# NixieDriver_overkill.net
KiCad netlist of a schematic drawn in EAGLE
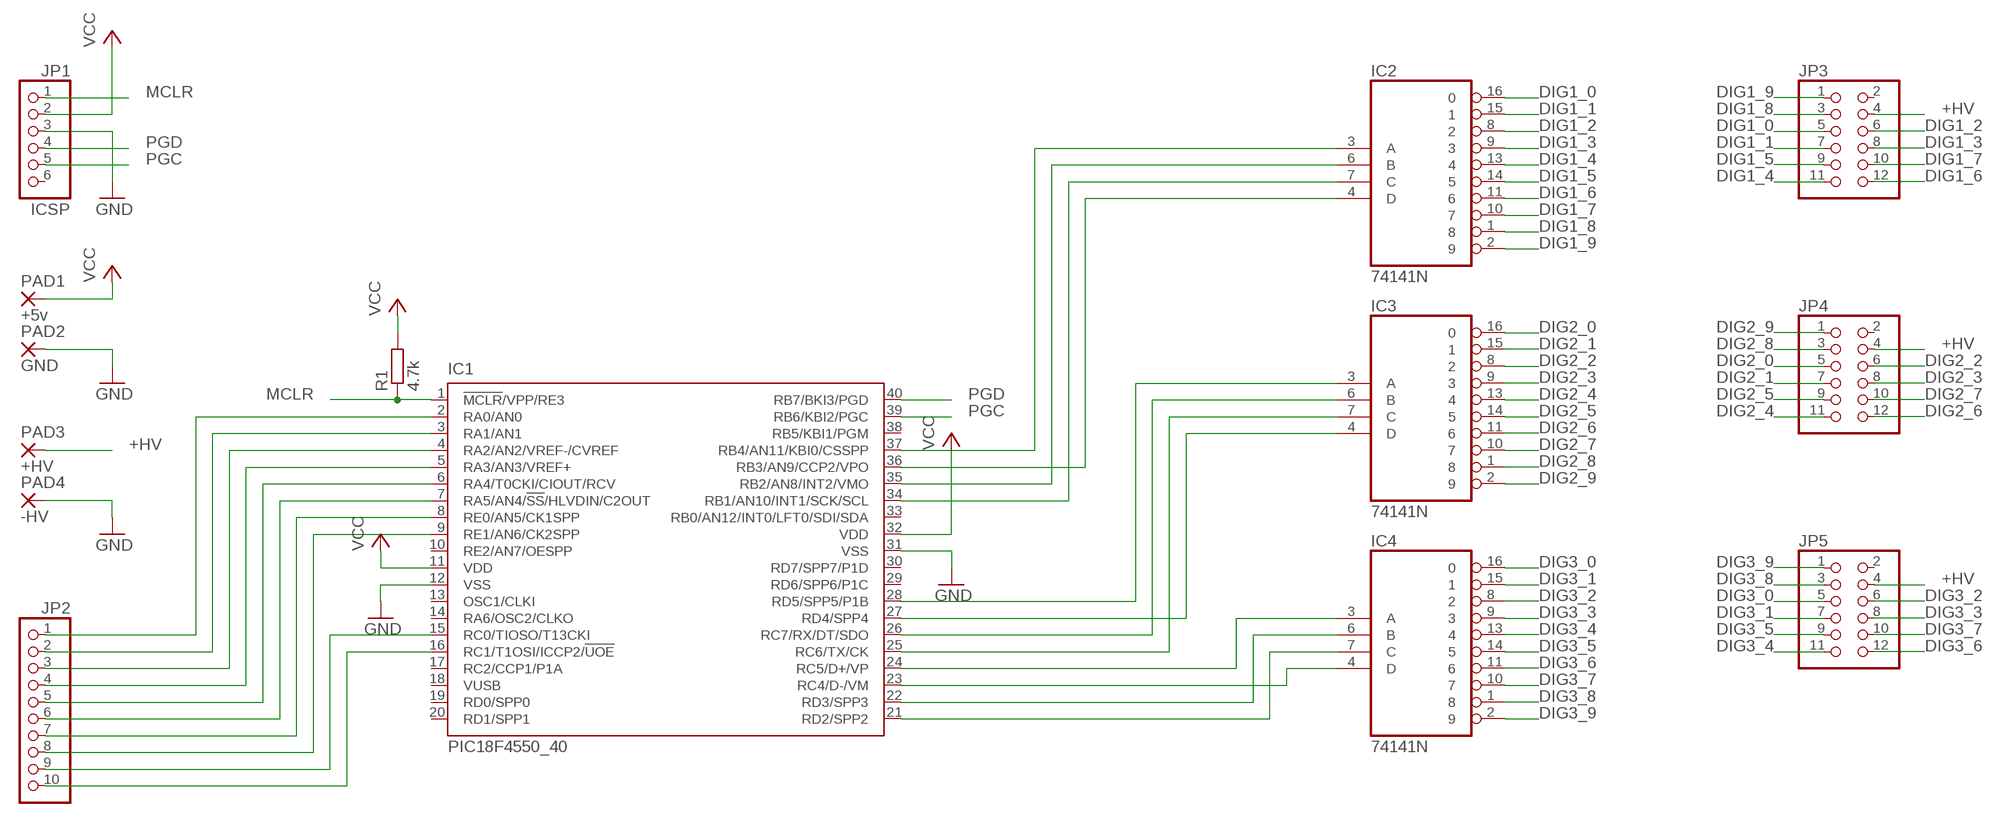
[diagram p0: schematic, sheet 1]

(export (version "E")
  (design (tool "Eeschema 10.0.6"))
  (components
    (comp (ref "IC1")
      (value "PIC18F4550_40")
      (footprint "eagle-import:DIL40")
      (fields (field (name "MF") "MICROCHIP") (field (name "MPN") "PIC18F4550-I/P"))
      (libsource (lib "eagle-import") (part "PIC18F4_40550"))
    )
    (comp (ref "IC2")
      (value "74141N")
      (footprint "eagle-import:DIL16")
      (libsource (lib "eagle-import") (part "74141N"))
    )
    (comp (ref "IC3")
      (value "74141N")
      (footprint "eagle-import:DIL16")
      (libsource (lib "eagle-import") (part "74141N"))
    )
    (comp (ref "IC4")
      (value "74141N")
      (footprint "eagle-import:DIL16")
      (libsource (lib "eagle-import") (part "74141N"))
    )
    (comp (ref "JP1")
      (value "ICSP")
      (footprint "eagle-import:1X06")
      (libsource (lib "eagle-import") (part "PINHD-1X6"))
    )
    (comp (ref "JP2")
      (value "PINHD-1X10")
      (footprint "eagle-import:1X10")
      (libsource (lib "eagle-import") (part "PINHD-1X10"))
    )
    (comp (ref "JP3")
      (value "PINHD-2X6")
      (footprint "eagle-import:2X06")
      (libsource (lib "eagle-import") (part "PINHD-2X6"))
    )
    (comp (ref "JP4")
      (value "PINHD-2X6")
      (footprint "eagle-import:2X06")
      (libsource (lib "eagle-import") (part "PINHD-2X6"))
    )
    (comp (ref "JP5")
      (value "PINHD-2X6")
      (footprint "eagle-import:2X06")
      (libsource (lib "eagle-import") (part "PINHD-2X6"))
    )
    (comp (ref "PAD1")
      (value "+5v")
      (footprint "eagle-import:SMD2,54-5,08")
      (libsource (lib "eagle-import") (part "SMD5"))
    )
    (comp (ref "PAD2")
      (value "GND")
      (footprint "eagle-import:SMD2,54-5,08")
      (libsource (lib "eagle-import") (part "SMD5"))
    )
    (comp (ref "PAD3")
      (value "+HV")
      (footprint "eagle-import:SMD2,54-5,08")
      (libsource (lib "eagle-import") (part "SMD5"))
    )
    (comp (ref "PAD4")
      (value "-HV")
      (footprint "eagle-import:SMD2,54-5,08")
      (libsource (lib "eagle-import") (part "SMD5"))
    )
    (comp (ref "R1")
      (value "4.7k")
      (footprint "eagle-import:R1206")
      (libsource (lib "eagle-import") (part "R-EU_R1206"))
    )
  )
  (nets
    (net (code "1") (name "/+HV") (class "Default")
      (node (ref "JP3") (pin "4") (pinfunction "4_4") (pintype "passive"))
      (node (ref "JP4") (pin "4") (pinfunction "4_4") (pintype "passive"))
      (node (ref "JP5") (pin "4") (pinfunction "4_4") (pintype "passive"))
      (node (ref "PAD3") (pin "1") (pinfunction "P_1") (pintype "passive"))
    )
    (net (code "2") (name "/DIG1_0") (class "Default")
      (node (ref "IC2") (pin "16") (pinfunction "0_16") (pintype "open_collector"))
      (node (ref "JP3") (pin "5") (pinfunction "5_5") (pintype "passive"))
    )
    (net (code "3") (name "/DIG1_1") (class "Default")
      (node (ref "IC2") (pin "15") (pinfunction "1_15") (pintype "open_collector"))
      (node (ref "JP3") (pin "7") (pinfunction "7_7") (pintype "passive"))
    )
    (net (code "4") (name "/DIG1_2") (class "Default")
      (node (ref "IC2") (pin "8") (pinfunction "2_8") (pintype "open_collector"))
      (node (ref "JP3") (pin "6") (pinfunction "6_6") (pintype "passive"))
    )
    (net (code "5") (name "/DIG1_3") (class "Default")
      (node (ref "IC2") (pin "9") (pinfunction "3_9") (pintype "open_collector"))
      (node (ref "JP3") (pin "8") (pinfunction "8_8") (pintype "passive"))
    )
    (net (code "6") (name "/DIG1_4") (class "Default")
      (node (ref "IC2") (pin "13") (pinfunction "4_13") (pintype "open_collector"))
      (node (ref "JP3") (pin "11") (pinfunction "11_11") (pintype "passive"))
    )
    (net (code "7") (name "/DIG1_5") (class "Default")
      (node (ref "IC2") (pin "14") (pinfunction "5_14") (pintype "open_collector"))
      (node (ref "JP3") (pin "9") (pinfunction "9_9") (pintype "passive"))
    )
    (net (code "8") (name "/DIG1_6") (class "Default")
      (node (ref "IC2") (pin "11") (pinfunction "6_11") (pintype "open_collector"))
      (node (ref "JP3") (pin "12") (pinfunction "12_12") (pintype "passive"))
    )
    (net (code "9") (name "/DIG1_7") (class "Default")
      (node (ref "IC2") (pin "10") (pinfunction "7_10") (pintype "open_collector"))
      (node (ref "JP3") (pin "10") (pinfunction "10_10") (pintype "passive"))
    )
    (net (code "10") (name "/DIG1_8") (class "Default")
      (node (ref "IC2") (pin "1") (pinfunction "8_1") (pintype "open_collector"))
      (node (ref "JP3") (pin "3") (pinfunction "3_3") (pintype "passive"))
    )
    (net (code "11") (name "/DIG1_9") (class "Default")
      (node (ref "IC2") (pin "2") (pinfunction "9_2") (pintype "open_collector"))
      (node (ref "JP3") (pin "1") (pinfunction "1_1") (pintype "passive"))
    )
    (net (code "12") (name "/DIG2_0") (class "Default")
      (node (ref "IC3") (pin "16") (pinfunction "0_16") (pintype "open_collector"))
      (node (ref "JP4") (pin "5") (pinfunction "5_5") (pintype "passive"))
    )
    (net (code "13") (name "/DIG2_1") (class "Default")
      (node (ref "IC3") (pin "15") (pinfunction "1_15") (pintype "open_collector"))
      (node (ref "JP4") (pin "7") (pinfunction "7_7") (pintype "passive"))
    )
    (net (code "14") (name "/DIG2_2") (class "Default")
      (node (ref "IC3") (pin "8") (pinfunction "2_8") (pintype "open_collector"))
      (node (ref "JP4") (pin "6") (pinfunction "6_6") (pintype "passive"))
    )
    (net (code "15") (name "/DIG2_3") (class "Default")
      (node (ref "IC3") (pin "9") (pinfunction "3_9") (pintype "open_collector"))
      (node (ref "JP4") (pin "8") (pinfunction "8_8") (pintype "passive"))
    )
    (net (code "16") (name "/DIG2_4") (class "Default")
      (node (ref "IC3") (pin "13") (pinfunction "4_13") (pintype "open_collector"))
      (node (ref "JP4") (pin "11") (pinfunction "11_11") (pintype "passive"))
    )
    (net (code "17") (name "/DIG2_5") (class "Default")
      (node (ref "IC3") (pin "14") (pinfunction "5_14") (pintype "open_collector"))
      (node (ref "JP4") (pin "9") (pinfunction "9_9") (pintype "passive"))
    )
    (net (code "18") (name "/DIG2_6") (class "Default")
      (node (ref "IC3") (pin "11") (pinfunction "6_11") (pintype "open_collector"))
      (node (ref "JP4") (pin "12") (pinfunction "12_12") (pintype "passive"))
    )
    (net (code "19") (name "/DIG2_7") (class "Default")
      (node (ref "IC3") (pin "10") (pinfunction "7_10") (pintype "open_collector"))
      (node (ref "JP4") (pin "10") (pinfunction "10_10") (pintype "passive"))
    )
    (net (code "20") (name "/DIG2_8") (class "Default")
      (node (ref "IC3") (pin "1") (pinfunction "8_1") (pintype "open_collector"))
      (node (ref "JP4") (pin "3") (pinfunction "3_3") (pintype "passive"))
    )
    (net (code "21") (name "/DIG2_9") (class "Default")
      (node (ref "IC3") (pin "2") (pinfunction "9_2") (pintype "open_collector"))
      (node (ref "JP4") (pin "1") (pinfunction "1_1") (pintype "passive"))
    )
    (net (code "22") (name "/DIG3_0") (class "Default")
      (node (ref "IC4") (pin "16") (pinfunction "0_16") (pintype "open_collector"))
      (node (ref "JP5") (pin "5") (pinfunction "5_5") (pintype "passive"))
    )
    (net (code "23") (name "/DIG3_1") (class "Default")
      (node (ref "IC4") (pin "15") (pinfunction "1_15") (pintype "open_collector"))
      (node (ref "JP5") (pin "7") (pinfunction "7_7") (pintype "passive"))
    )
    (net (code "24") (name "/DIG3_2") (class "Default")
      (node (ref "IC4") (pin "8") (pinfunction "2_8") (pintype "open_collector"))
      (node (ref "JP5") (pin "6") (pinfunction "6_6") (pintype "passive"))
    )
    (net (code "25") (name "/DIG3_3") (class "Default")
      (node (ref "IC4") (pin "9") (pinfunction "3_9") (pintype "open_collector"))
      (node (ref "JP5") (pin "8") (pinfunction "8_8") (pintype "passive"))
    )
    (net (code "26") (name "/DIG3_4") (class "Default")
      (node (ref "IC4") (pin "13") (pinfunction "4_13") (pintype "open_collector"))
      (node (ref "JP5") (pin "11") (pinfunction "11_11") (pintype "passive"))
    )
    (net (code "27") (name "/DIG3_5") (class "Default")
      (node (ref "IC4") (pin "14") (pinfunction "5_14") (pintype "open_collector"))
      (node (ref "JP5") (pin "9") (pinfunction "9_9") (pintype "passive"))
    )
    (net (code "28") (name "/DIG3_6") (class "Default")
      (node (ref "IC4") (pin "11") (pinfunction "6_11") (pintype "open_collector"))
      (node (ref "JP5") (pin "12") (pinfunction "12_12") (pintype "passive"))
    )
    (net (code "29") (name "/DIG3_7") (class "Default")
      (node (ref "IC4") (pin "10") (pinfunction "7_10") (pintype "open_collector"))
      (node (ref "JP5") (pin "10") (pinfunction "10_10") (pintype "passive"))
    )
    (net (code "30") (name "/DIG3_8") (class "Default")
      (node (ref "IC4") (pin "1") (pinfunction "8_1") (pintype "open_collector"))
      (node (ref "JP5") (pin "3") (pinfunction "3_3") (pintype "passive"))
    )
    (net (code "31") (name "/DIG3_9") (class "Default")
      (node (ref "IC4") (pin "2") (pinfunction "9_2") (pintype "open_collector"))
      (node (ref "JP5") (pin "1") (pinfunction "1_1") (pintype "passive"))
    )
    (net (code "32") (name "/MCLR") (class "Default")
      (node (ref "IC1") (pin "1") (pinfunction "~{MCLR}/VPP/RE3_1") (pintype "input"))
      (node (ref "JP1") (pin "1") (pinfunction "1_1") (pintype "passive"))
      (node (ref "R1") (pin "1") (pinfunction "1_1") (pintype "passive"))
    )
    (net (code "33") (name "/PGC") (class "Default")
      (node (ref "IC1") (pin "39") (pinfunction "RB6/KBI2/PGC_39") (pintype "bidirectional"))
      (node (ref "JP1") (pin "5") (pinfunction "5_5") (pintype "passive"))
    )
    (net (code "34") (name "/PGD") (class "Default")
      (node (ref "IC1") (pin "40") (pinfunction "RB7/BKI3/PGD_40") (pintype "bidirectional"))
      (node (ref "JP1") (pin "4") (pinfunction "4_4") (pintype "passive"))
    )
    (net (code "35") (name "GND") (class "Default")
      (node (ref "IC1") (pin "12") (pinfunction "VSS_12") (pintype "power_in"))
      (node (ref "IC1") (pin "31") (pinfunction "VSS_31") (pintype "power_in"))
      (node (ref "JP1") (pin "3") (pinfunction "3_3") (pintype "passive"))
      (node (ref "PAD2") (pin "1") (pinfunction "P_1") (pintype "passive"))
      (node (ref "PAD4") (pin "1") (pinfunction "P_1") (pintype "passive"))
    )
    (net (code "36") (name "Net-(IC1-RA0{slash}AN0)") (class "Default")
      (node (ref "IC1") (pin "2") (pinfunction "RA0/AN0_2") (pintype "bidirectional"))
      (node (ref "JP2") (pin "1") (pinfunction "1_1") (pintype "passive"))
    )
    (net (code "37") (name "Net-(IC1-RA1{slash}AN1)") (class "Default")
      (node (ref "IC1") (pin "3") (pinfunction "RA1/AN1_3") (pintype "bidirectional"))
      (node (ref "JP2") (pin "2") (pinfunction "2_2") (pintype "passive"))
    )
    (net (code "38") (name "Net-(IC1-RA2{slash}AN2{slash}VREF-{slash}CVREF)") (class "Default")
      (node (ref "IC1") (pin "4") (pinfunction "RA2/AN2/VREF-/CVREF_4") (pintype "bidirectional"))
      (node (ref "JP2") (pin "3") (pinfunction "3_3") (pintype "passive"))
    )
    (net (code "39") (name "Net-(IC1-RA3{slash}AN3{slash}VREF+)") (class "Default")
      (node (ref "IC1") (pin "5") (pinfunction "RA3/AN3/VREF+_5") (pintype "bidirectional"))
      (node (ref "JP2") (pin "4") (pinfunction "4_4") (pintype "passive"))
    )
    (net (code "40") (name "Net-(IC1-RA4{slash}T0CKI{slash}CIOUT{slash}RCV)") (class "Default")
      (node (ref "IC1") (pin "6") (pinfunction "RA4/T0CKI/CIOUT/RCV_6") (pintype "bidirectional"))
      (node (ref "JP2") (pin "5") (pinfunction "5_5") (pintype "passive"))
    )
    (net (code "41") (name "Net-(IC1-RA5{slash}AN4{slash}~{SS}{slash}HLVDIN{slash}C2OUT)") (class "Default")
      (node (ref "IC1") (pin "7") (pinfunction "RA5/AN4/~{SS}/HLVDIN/C2OUT_7") (pintype "bidirectional"))
      (node (ref "JP2") (pin "6") (pinfunction "6_6") (pintype "passive"))
    )
    (net (code "42") (name "Net-(IC1-RB1{slash}AN10{slash}INT1{slash}SCK{slash}SCL)") (class "Default")
      (node (ref "IC1") (pin "34") (pinfunction "RB1/AN10/INT1/SCK/SCL_34") (pintype "bidirectional"))
      (node (ref "IC2") (pin "7") (pinfunction "C_7") (pintype "input"))
    )
    (net (code "43") (name "Net-(IC1-RB2{slash}AN8{slash}INT2{slash}VMO)") (class "Default")
      (node (ref "IC1") (pin "35") (pinfunction "RB2/AN8/INT2/VMO_35") (pintype "bidirectional"))
      (node (ref "IC2") (pin "6") (pinfunction "B_6") (pintype "input"))
    )
    (net (code "44") (name "Net-(IC1-RB3{slash}AN9{slash}CCP2{slash}VPO)") (class "Default")
      (node (ref "IC1") (pin "36") (pinfunction "RB3/AN9/CCP2/VPO_36") (pintype "bidirectional"))
      (node (ref "IC2") (pin "4") (pinfunction "D_4") (pintype "input"))
    )
    (net (code "45") (name "Net-(IC1-RB4{slash}AN11{slash}KBI0{slash}CSSPP)") (class "Default")
      (node (ref "IC1") (pin "37") (pinfunction "RB4/AN11/KBI0/CSSPP_37") (pintype "bidirectional"))
      (node (ref "IC2") (pin "3") (pinfunction "A_3") (pintype "input"))
    )
    (net (code "46") (name "Net-(IC1-RC0{slash}TIOSO{slash}T13CKI)") (class "Default")
      (node (ref "IC1") (pin "15") (pinfunction "RC0/TIOSO/T13CKI_15") (pintype "bidirectional"))
      (node (ref "JP2") (pin "9") (pinfunction "9_9") (pintype "passive"))
    )
    (net (code "47") (name "Net-(IC1-RC1{slash}T1OSI{slash}ICCP2{slash}~{UOE})") (class "Default")
      (node (ref "IC1") (pin "16") (pinfunction "RC1/T1OSI/ICCP2/~{UOE}_16") (pintype "bidirectional"))
      (node (ref "JP2") (pin "10") (pinfunction "10_10") (pintype "passive"))
    )
    (net (code "48") (name "Net-(IC1-RC4{slash}D-{slash}VM)") (class "Default")
      (node (ref "IC1") (pin "23") (pinfunction "RC4/D-/VM_23") (pintype "bidirectional"))
      (node (ref "IC4") (pin "4") (pinfunction "D_4") (pintype "input"))
    )
    (net (code "49") (name "Net-(IC1-RC5{slash}D+{slash}VP)") (class "Default")
      (node (ref "IC1") (pin "24") (pinfunction "RC5/D+/VP_24") (pintype "bidirectional"))
      (node (ref "IC4") (pin "3") (pinfunction "A_3") (pintype "input"))
    )
    (net (code "50") (name "Net-(IC1-RC6{slash}TX{slash}CK)") (class "Default")
      (node (ref "IC1") (pin "25") (pinfunction "RC6/TX/CK_25") (pintype "bidirectional"))
      (node (ref "IC3") (pin "7") (pinfunction "C_7") (pintype "input"))
    )
    (net (code "51") (name "Net-(IC1-RC7{slash}RX{slash}DT{slash}SDO)") (class "Default")
      (node (ref "IC1") (pin "26") (pinfunction "RC7/RX/DT/SDO_26") (pintype "bidirectional"))
      (node (ref "IC3") (pin "6") (pinfunction "B_6") (pintype "input"))
    )
    (net (code "52") (name "Net-(IC1-RD2{slash}SPP2)") (class "Default")
      (node (ref "IC1") (pin "21") (pinfunction "RD2/SPP2_21") (pintype "bidirectional"))
      (node (ref "IC4") (pin "7") (pinfunction "C_7") (pintype "input"))
    )
    (net (code "53") (name "Net-(IC1-RD3{slash}SPP3)") (class "Default")
      (node (ref "IC1") (pin "22") (pinfunction "RD3/SPP3_22") (pintype "bidirectional"))
      (node (ref "IC4") (pin "6") (pinfunction "B_6") (pintype "input"))
    )
    (net (code "54") (name "Net-(IC1-RD4{slash}SPP4)") (class "Default")
      (node (ref "IC1") (pin "27") (pinfunction "RD4/SPP4_27") (pintype "bidirectional"))
      (node (ref "IC3") (pin "4") (pinfunction "D_4") (pintype "input"))
    )
    (net (code "55") (name "Net-(IC1-RD5{slash}SPP5{slash}P1B)") (class "Default")
      (node (ref "IC1") (pin "28") (pinfunction "RD5/SPP5/P1B_28") (pintype "bidirectional"))
      (node (ref "IC3") (pin "3") (pinfunction "A_3") (pintype "input"))
    )
    (net (code "56") (name "Net-(IC1-RE0{slash}AN5{slash}CK1SPP)") (class "Default")
      (node (ref "IC1") (pin "8") (pinfunction "RE0/AN5/CK1SPP_8") (pintype "bidirectional"))
      (node (ref "JP2") (pin "7") (pinfunction "7_7") (pintype "passive"))
    )
    (net (code "57") (name "Net-(IC1-RE1{slash}AN6{slash}CK2SPP)") (class "Default")
      (node (ref "IC1") (pin "9") (pinfunction "RE1/AN6/CK2SPP_9") (pintype "bidirectional"))
      (node (ref "JP2") (pin "8") (pinfunction "8_8") (pintype "passive"))
    )
    (net (code "58") (name "VCC") (class "Default")
      (node (ref "IC1") (pin "11") (pinfunction "VDD_11") (pintype "power_in"))
      (node (ref "IC1") (pin "32") (pinfunction "VDD_32") (pintype "power_in"))
      (node (ref "JP1") (pin "2") (pinfunction "2_2") (pintype "passive"))
      (node (ref "PAD1") (pin "1") (pinfunction "P_1") (pintype "passive"))
      (node (ref "R1") (pin "2") (pinfunction "2_2") (pintype "passive"))
    )
    (net (code "59") (name "unconnected-(IC1-OSC1{slash}CLKI-Pad13)") (class "Default")
      (node (ref "IC1") (pin "13") (pinfunction "OSC1/CLKI_13") (pintype "input"))
    )
    (net (code "60") (name "unconnected-(IC1-RA6{slash}OSC2{slash}CLKO-Pad14)") (class "Default")
      (node (ref "IC1") (pin "14") (pinfunction "RA6/OSC2/CLKO_14") (pintype "output"))
    )
    (net (code "61") (name "unconnected-(IC1-RB0{slash}AN12{slash}INT0{slash}LFT0{slash}SDI{slash}SDA-Pad33)") (class "Default")
      (node (ref "IC1") (pin "33") (pinfunction "RB0/AN12/INT0/LFT0/SDI/SDA_33") (pintype "bidirectional"))
    )
    (net (code "62") (name "unconnected-(IC1-RB5{slash}KBI1{slash}PGM-Pad38)") (class "Default")
      (node (ref "IC1") (pin "38") (pinfunction "RB5/KBI1/PGM_38") (pintype "bidirectional"))
    )
    (net (code "63") (name "unconnected-(IC1-RC2{slash}CCP1{slash}P1A-Pad17)") (class "Default")
      (node (ref "IC1") (pin "17") (pinfunction "RC2/CCP1/P1A_17") (pintype "bidirectional"))
    )
    (net (code "64") (name "unconnected-(IC1-RD0{slash}SPP0-Pad19)") (class "Default")
      (node (ref "IC1") (pin "19") (pinfunction "RD0/SPP0_19") (pintype "bidirectional"))
    )
    (net (code "65") (name "unconnected-(IC1-RD1{slash}SPP1-Pad20)") (class "Default")
      (node (ref "IC1") (pin "20") (pinfunction "RD1/SPP1_20") (pintype "bidirectional"))
    )
    (net (code "66") (name "unconnected-(IC1-RD6{slash}SPP6{slash}P1C-Pad29)") (class "Default")
      (node (ref "IC1") (pin "29") (pinfunction "RD6/SPP6/P1C_29") (pintype "bidirectional"))
    )
    (net (code "67") (name "unconnected-(IC1-RD7{slash}SPP7{slash}P1D-Pad30)") (class "Default")
      (node (ref "IC1") (pin "30") (pinfunction "RD7/SPP7/P1D_30") (pintype "bidirectional"))
    )
    (net (code "68") (name "unconnected-(IC1-RE2{slash}AN7{slash}OESPP-Pad10)") (class "Default")
      (node (ref "IC1") (pin "10") (pinfunction "RE2/AN7/OESPP_10") (pintype "bidirectional"))
    )
    (net (code "69") (name "unconnected-(IC1-VUSB-Pad18)") (class "Default")
      (node (ref "IC1") (pin "18") (pinfunction "VUSB_18") (pintype "bidirectional"))
    )
    (net (code "70") (name "unconnected-(JP1-Pad6)") (class "Default")
      (node (ref "JP1") (pin "6") (pinfunction "6_6") (pintype "passive"))
    )
    (net (code "71") (name "unconnected-(JP3-Pad2)") (class "Default")
      (node (ref "JP3") (pin "2") (pinfunction "2_2") (pintype "passive"))
    )
    (net (code "72") (name "unconnected-(JP4-Pad2)") (class "Default")
      (node (ref "JP4") (pin "2") (pinfunction "2_2") (pintype "passive"))
    )
    (net (code "73") (name "unconnected-(JP5-Pad2)") (class "Default")
      (node (ref "JP5") (pin "2") (pinfunction "2_2") (pintype "passive"))
    )
  )
)
